# Sheet1.net
KiCad netlist of a schematic drawn in Altium Designer
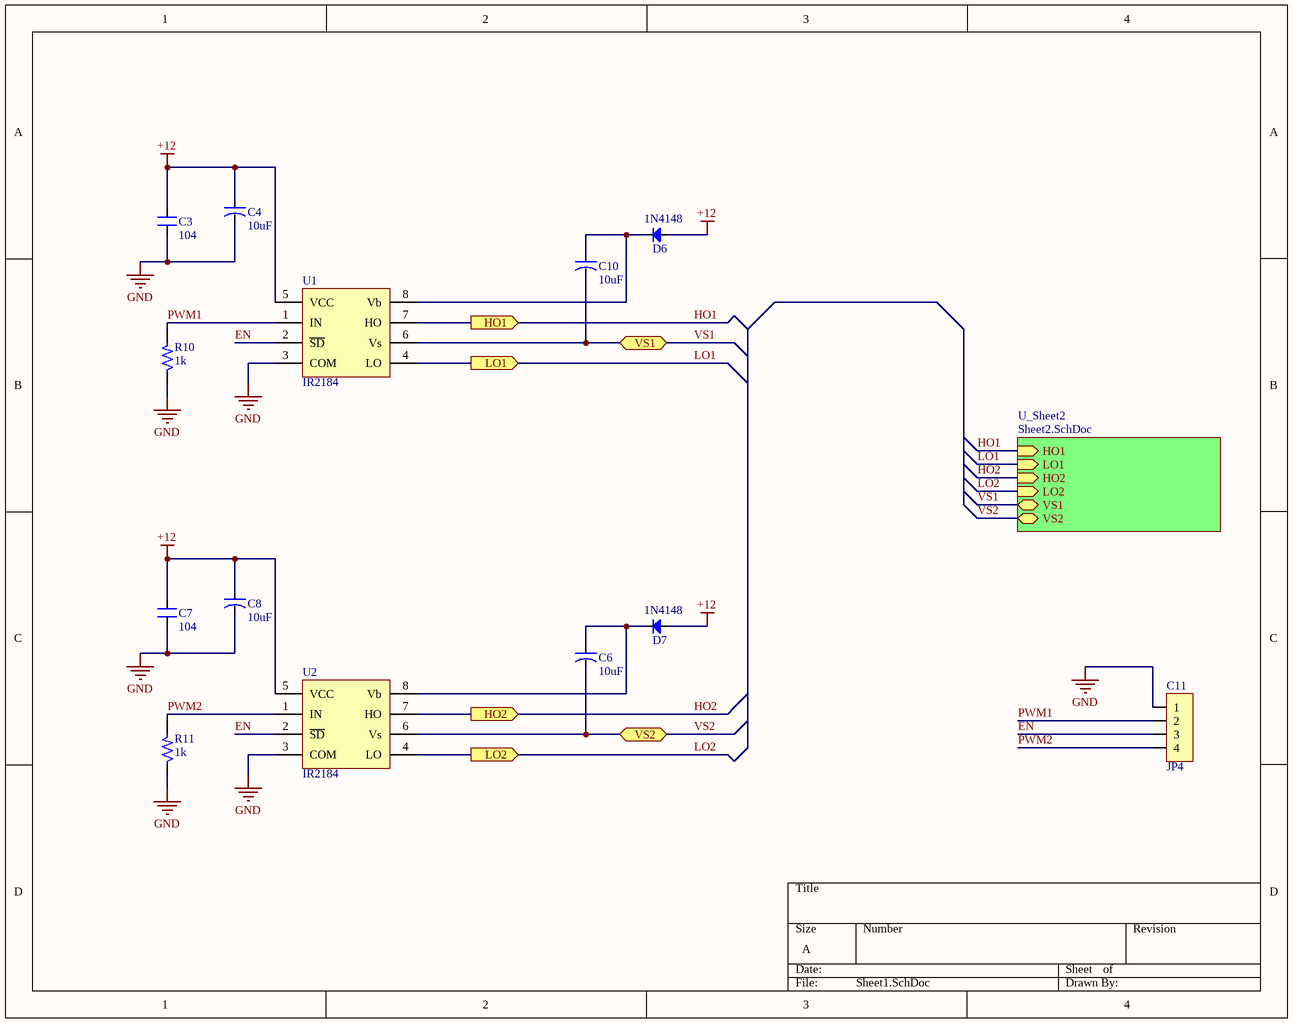
[diagram p0: Sheet1.SchDoc]

(export (version "E")
  (design (tool "Eeschema 10.0.6"))
  (components
    (comp (ref "C3")
      (value "104")
      (footprint "SM-CAP-0805")
      (fields (field (name "DESIGNED BY") "VanDungEvn"))
      (libsource (lib "echipkool-com-library") (part "CN"))
    )
    (comp (ref "C4")
      (value "10uF")
      (footprint "CAP-ALU-SMD-4.5x5x1.4")
      (description "Polarized Capacitor (Axial)")
      (fields (field (name "PUBLISHER") "Altium Limited"))
      (libsource (lib "LIBRARYALT") (part "CN-ALU-SMD"))
    )
    (comp (ref "C6")
      (value "10uF")
      (footprint "CAP-ALU-SMD-4.5x5x1.4")
      (description "Polarized Capacitor (Axial)")
      (fields (field (name "PUBLISHER") "Altium Limited"))
      (libsource (lib "LIBRARYALT") (part "CN-ALU-SMD"))
    )
    (comp (ref "C7")
      (value "104")
      (footprint "SM-CAP-0805")
      (fields (field (name "DESIGNED BY") "VanDungEvn"))
      (libsource (lib "echipkool-com-library") (part "CN"))
    )
    (comp (ref "C8")
      (value "10uF")
      (footprint "CAP-ALU-SMD-4.5x5x1.4")
      (description "Polarized Capacitor (Axial)")
      (fields (field (name "PUBLISHER") "Altium Limited"))
      (libsource (lib "LIBRARYALT") (part "CN-ALU-SMD"))
    )
    (comp (ref "C10")
      (value "10uF")
      (footprint "CAP-ALU-SMD-4.5x5x1.4")
      (description "Polarized Capacitor (Axial)")
      (fields (field (name "PUBLISHER") "Altium Limited"))
      (libsource (lib "LIBRARYALT") (part "CN-ALU-SMD"))
    )
    (comp (ref "C11")
      (value "JP4")
      (footprint "JP4-C1T")
      (description "WR-PHD 2.54 mm Angled Socket Header")
      (fields
        (field (name "MANUFACTURER") "Würth Elektronik eiSos GmbH")
        (field (name "PARTNO") "613004143121")
        (field (name "CREATED BY") "Karrer Zheng")
      )
      (libsource (lib "LIBRARYALT") (part "JP4"))
    )
    (comp (ref "D6")
      (value "1N4148")
      (footprint "DIO-SMD-106")
      (description "Default Diode")
      (fields (field (name "PUBLISHER") "Altium Limited"))
      (libsource (lib "LIBRARYALT") (part "Diode SMD"))
    )
    (comp (ref "D7")
      (value "1N4148")
      (footprint "DIO-SMD-106")
      (description "Default Diode")
      (fields (field (name "PUBLISHER") "Altium Limited"))
      (libsource (lib "LIBRARYALT") (part "Diode SMD"))
    )
    (comp (ref "R10")
      (value "1k")
      (footprint "SM-RES-1206")
      (description "Resistor 1/4W")
      (libsource (lib "echipkool-com-library") (part "R"))
    )
    (comp (ref "R11")
      (value "1k")
      (footprint "SM-RES-1206")
      (description "Resistor 1/4W")
      (libsource (lib "echipkool-com-library") (part "R"))
    )
    (comp (ref "U1")
      (value "IR2184")
      (footprint "SO8")
      (description "Half-Bridge Driver")
      (libsource (lib "LIBRARYALT") (part "IR2184"))
    )
    (comp (ref "U2")
      (value "IR2184")
      (footprint "SO8")
      (description "Half-Bridge Driver")
      (libsource (lib "LIBRARYALT") (part "IR2184"))
    )
  )
  (nets
    (net (code "1") (name "+12") (class "Default")
      (node (ref "C3") (pin "2") (pinfunction "2_2") (pintype "passive"))
      (node (ref "C4") (pin "1") (pinfunction "1_1") (pintype "passive"))
      (node (ref "C7") (pin "2") (pinfunction "2_2") (pintype "passive"))
      (node (ref "C8") (pin "1") (pinfunction "1_1") (pintype "passive"))
      (node (ref "D6") (pin "1") (pinfunction "A_1") (pintype "passive"))
      (node (ref "D7") (pin "1") (pinfunction "A_1") (pintype "passive"))
      (node (ref "U1") (pin "5") (pinfunction "VCC_5") (pintype "passive"))
      (node (ref "U2") (pin "5") (pinfunction "VCC_5") (pintype "passive"))
    )
    (net (code "2") (name "/EN") (class "Default")
      (node (ref "C11") (pin "3") (pinfunction "3_3") (pintype "passive"))
      (node (ref "U1") (pin "2") (pinfunction "~{SD}_2") (pintype "passive"))
      (node (ref "U2") (pin "2") (pinfunction "~{SD}_2") (pintype "passive"))
    )
    (net (code "3") (name "/HO1") (class "Default")
      (node (ref "U1") (pin "7") (pinfunction "HO_7") (pintype "passive"))
    )
    (net (code "4") (name "/HO2") (class "Default")
      (node (ref "U2") (pin "7") (pinfunction "HO_7") (pintype "passive"))
    )
    (net (code "5") (name "/LO1") (class "Default")
      (node (ref "U1") (pin "4") (pinfunction "LO_4") (pintype "passive"))
    )
    (net (code "6") (name "/LO2") (class "Default")
      (node (ref "U2") (pin "4") (pinfunction "LO_4") (pintype "passive"))
    )
    (net (code "7") (name "/PWM1") (class "Default")
      (node (ref "C11") (pin "2") (pinfunction "2_2") (pintype "passive"))
      (node (ref "R10") (pin "2") (pinfunction "2_2") (pintype "passive"))
      (node (ref "U1") (pin "1") (pinfunction "IN_1") (pintype "passive"))
    )
    (net (code "8") (name "/PWM2") (class "Default")
      (node (ref "C11") (pin "4") (pinfunction "4_4") (pintype "passive"))
      (node (ref "R11") (pin "2") (pinfunction "2_2") (pintype "passive"))
      (node (ref "U2") (pin "1") (pinfunction "IN_1") (pintype "passive"))
    )
    (net (code "9") (name "/VS1") (class "Default")
      (node (ref "C10") (pin "2") (pinfunction "2_2") (pintype "passive"))
      (node (ref "U1") (pin "6") (pinfunction "Vs_6") (pintype "passive"))
    )
    (net (code "10") (name "/VS2") (class "Default")
      (node (ref "C6") (pin "2") (pinfunction "2_2") (pintype "passive"))
      (node (ref "U2") (pin "6") (pinfunction "Vs_6") (pintype "passive"))
    )
    (net (code "11") (name "GND") (class "Default")
      (node (ref "C11") (pin "1") (pinfunction "1_1") (pintype "passive"))
      (node (ref "C3") (pin "1") (pinfunction "1_1") (pintype "passive"))
      (node (ref "C4") (pin "2") (pinfunction "2_2") (pintype "passive"))
      (node (ref "C7") (pin "1") (pinfunction "1_1") (pintype "passive"))
      (node (ref "C8") (pin "2") (pinfunction "2_2") (pintype "passive"))
      (node (ref "R10") (pin "1") (pinfunction "1_1") (pintype "passive"))
      (node (ref "R11") (pin "1") (pinfunction "1_1") (pintype "passive"))
      (node (ref "U1") (pin "3") (pinfunction "COM_3") (pintype "passive"))
      (node (ref "U2") (pin "3") (pinfunction "COM_3") (pintype "passive"))
    )
    (net (code "12") (name "Net-(D6-K)") (class "Default")
      (node (ref "C10") (pin "1") (pinfunction "1_1") (pintype "passive"))
      (node (ref "D6") (pin "2") (pinfunction "K_2") (pintype "passive"))
      (node (ref "U1") (pin "8") (pinfunction "Vb_8") (pintype "passive"))
    )
    (net (code "13") (name "Net-(D7-K)") (class "Default")
      (node (ref "C6") (pin "1") (pinfunction "1_1") (pintype "passive"))
      (node (ref "D7") (pin "2") (pinfunction "K_2") (pintype "passive"))
      (node (ref "U2") (pin "8") (pinfunction "Vb_8") (pintype "passive"))
    )
  )
)
